# GRHV_4_Tube_v0_1.net
KiCad netlist of a schematic drawn in Altium Designer
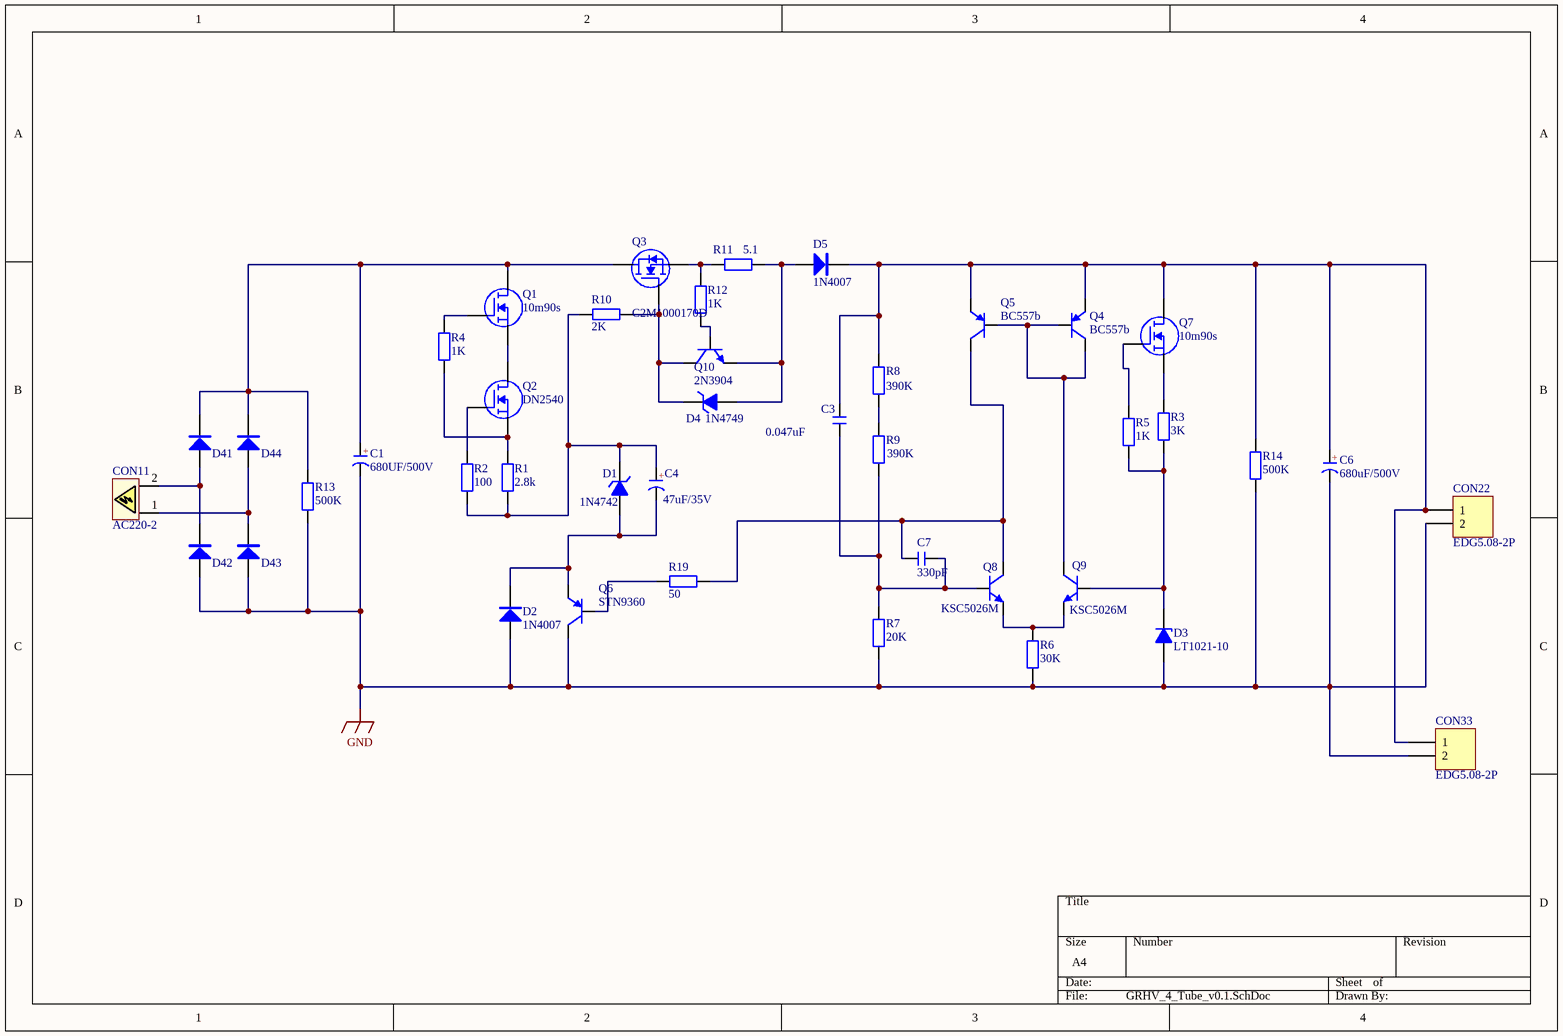
[diagram p0: GRHV_4_Tube_v0.1.SchDoc]

(export (version "E")
  (design (tool "Eeschema 10.0.6"))
  (components
    (comp (ref "C1")
      (value "680UF/500V")
      (footprint "CAP 11*35*60")
      (description "直插电解电容")
      (fields (field (name "版权归属") "源创客"))
      (libsource (lib "电阻-电容-电感") (part "C-CAP"))
    )
    (comp (ref "C3")
      (value "0.047uF")
      (footprint "CBB 15*18*11")
      (description "CBB电容")
      (fields (field (name "版权归属") "源创客"))
      (libsource (lib "电阻-电容-电感") (part "C-CBB"))
    )
    (comp (ref "C4")
      (value "47uF/35V")
      (footprint "CAP 5.0*10*12.5")
      (description "直插电解电容")
      (fields (field (name "版权归属") "源创客"))
      (libsource (lib "电阻-电容-电感") (part "C-CAP"))
    )
    (comp (ref "C6")
      (value "680uF/500V")
      (footprint "CAP 11*35*60")
      (description "直插电解电容")
      (fields (field (name "版权归属") "源创客"))
      (libsource (lib "电阻-电容-电感") (part "C-CAP"))
    )
    (comp (ref "C7")
      (value "330pF")
      (footprint "CBB 6.3*6.3*5")
      (description "CBB电容")
      (fields (field (name "版权归属") "源创客"))
      (libsource (lib "电阻-电容-电感") (part "C-CBB"))
    )
    (comp (ref "CON11")
      (value "AC220-2")
      (footprint "HX5.08-2S")
      (libsource (lib "Connectors") (part "AC220-2"))
    )
    (comp (ref "CON22")
      (value "EDG5.08-2P")
      (footprint "HX5.08-2L")
      (libsource (lib "Connectors") (part "EDG5.08-2P"))
    )
    (comp (ref "CON33")
      (value "EDG5.08-2P")
      (footprint "HX5.08-2L")
      (libsource (lib "Connectors") (part "EDG5.08-2P"))
    )
    (comp (ref "D1")
      (value "1N4742")
      (footprint "DO-41")
      (description "12V/1W稳压管")
      (libsource (lib "二极管-整流桥") (part "1N4742"))
    )
    (comp (ref "D2")
      (value "1N4007")
      (footprint "DO-41")
      (description "整流二极管")
      (fields (field (name "版权归属") "源创客"))
      (libsource (lib "二极管-整流桥") (part "1N4007"))
    )
    (comp (ref "D3")
      (value "LT1021-10")
      (footprint "DIP8-300_MH")
      (description "10V Precision Reference 2 Pin Config")
      (libsource (lib "电压参考") (part "LT1021-10-2P"))
    )
    (comp (ref "D4")
      (value "1N4749")
      (footprint "DO-41")
      (description "24V/1W稳压管")
      (libsource (lib "二极管-整流桥") (part "1N4749"))
    )
    (comp (ref "D5")
      (value "1N4007")
      (footprint "DO-41")
      (description "整流二极管")
      (fields (field (name "版权归属") "源创客"))
      (libsource (lib "二极管-整流桥") (part "1N4007"))
    )
    (comp (ref "D41")
      (value "VS-HFA08TB60-M3")
      (footprint "TO220AC")
      (description "Ultrafast Soft Recovery Diado 8A 600V")
      (libsource (lib "二极管-整流桥") (part "VS-HFA08TB60-M3"))
    )
    (comp (ref "D42")
      (value "VS-HFA08TB60-M3")
      (footprint "TO220AC")
      (description "Ultrafast Soft Recovery Diado 8A 600V")
      (libsource (lib "二极管-整流桥") (part "VS-HFA08TB60-M3"))
    )
    (comp (ref "D43")
      (value "VS-HFA08TB60-M3")
      (footprint "TO220AC")
      (description "Ultrafast Soft Recovery Diado 8A 600V")
      (libsource (lib "二极管-整流桥") (part "VS-HFA08TB60-M3"))
    )
    (comp (ref "D44")
      (value "VS-HFA08TB60-M3")
      (footprint "TO220AC")
      (description "Ultrafast Soft Recovery Diado 8A 600V")
      (libsource (lib "二极管-整流桥") (part "VS-HFA08TB60-M3"))
    )
    (comp (ref "Q1")
      (value "10m90s")
      (footprint "TO220H")
      (description "IC恒流源  900v 100ma")
      (libsource (lib "场效应管") (part "10m90s"))
    )
    (comp (ref "Q2")
      (value "DN2540")
      (footprint "TO220V")
      (description "N沟道耗尽型DMOS场效应管 400V/150ma")
      (libsource (lib "场效应管") (part "DN2540"))
    )
    (comp (ref "Q3")
      (value "C2M1000170D")
      (footprint "TO247H")
      (description "N沟道增强型 Z-FET MOS场效应管 1000v 5A")
      (libsource (lib "场效应管") (part "C2M1000170D"))
    )
    (comp (ref "Q4")
      (value "BC557b")
      (footprint "TO92A")
      (description "音频放大-PNP型")
      (libsource (lib "三极管") (part "BC557b"))
    )
    (comp (ref "Q5")
      (value "BC557b")
      (footprint "TO92A")
      (description "音频放大-PNP型")
      (libsource (lib "三极管") (part "BC557b"))
    )
    (comp (ref "Q6")
      (value "STN9360")
      (footprint "SOT223_L_Bottom")
      (description "High Voltage fast switching PNP型 600v 500ma")
      (libsource (lib "三极管") (part "STN9360"))
    )
    (comp (ref "Q7")
      (value "10m90s")
      (footprint "TO220H")
      (description "IC恒流源  900v 100ma")
      (libsource (lib "场效应管") (part "10m90s"))
    )
    (comp (ref "Q8")
      (value "KSC5026M")
      (footprint "TO126V")
      (description "High Speed Switch -NPN型")
      (libsource (lib "三极管") (part "KSC5026M"))
    )
    (comp (ref "Q9")
      (value "KSC5026M")
      (footprint "TO126V")
      (description "High Speed Switch -NPN型")
      (libsource (lib "三极管") (part "KSC5026M"))
    )
    (comp (ref "Q10")
      (value "2N3904")
      (footprint "TO92A")
      (description "通用三极管NPN型 40v 200ma")
      (libsource (lib "三极管") (part "2N3904"))
    )
    (comp (ref "R1")
      (value "2.8k")
      (footprint "RS 1W")
      (description "直插色环电阻")
      (fields (field (name "版权归属") "源创客"))
      (libsource (lib "电阻-电容-电感") (part "R-CRR"))
    )
    (comp (ref "R2")
      (value "100")
      (footprint "RS 1W")
      (description "直插色环电阻")
      (fields (field (name "版权归属") "源创客"))
      (libsource (lib "电阻-电容-电感") (part "R-CRR"))
    )
    (comp (ref "R3")
      (value "3K")
      (footprint "RS 1W")
      (description "直插色环电阻")
      (fields (field (name "版权归属") "源创客"))
      (libsource (lib "电阻-电容-电感") (part "R-CRR"))
    )
    (comp (ref "R4")
      (value "1K")
      (footprint "RS 1W")
      (description "直插色环电阻")
      (fields (field (name "版权归属") "源创客"))
      (libsource (lib "电阻-电容-电感") (part "R-CRR"))
    )
    (comp (ref "R5")
      (value "1K")
      (footprint "RS 1W")
      (description "直插色环电阻")
      (fields (field (name "版权归属") "源创客"))
      (libsource (lib "电阻-电容-电感") (part "R-CRR"))
    )
    (comp (ref "R6")
      (value "30K")
      (footprint "RS 1W")
      (description "直插色环电阻")
      (fields (field (name "版权归属") "源创客"))
      (libsource (lib "电阻-电容-电感") (part "R-CRR"))
    )
    (comp (ref "R7")
      (value "20K")
      (footprint "RS 1W")
      (description "直插色环电阻")
      (fields (field (name "版权归属") "源创客"))
      (libsource (lib "电阻-电容-电感") (part "R-CRR"))
    )
    (comp (ref "R8")
      (value "390K")
      (footprint "RS 1W")
      (description "直插色环电阻")
      (fields (field (name "版权归属") "源创客"))
      (libsource (lib "电阻-电容-电感") (part "R-CRR"))
    )
    (comp (ref "R9")
      (value "390K")
      (footprint "RS 1W")
      (description "直插色环电阻")
      (fields (field (name "版权归属") "源创客"))
      (libsource (lib "电阻-电容-电感") (part "R-CRR"))
    )
    (comp (ref "R10")
      (value "2K")
      (footprint "RS 1W")
      (description "直插色环电阻")
      (fields (field (name "版权归属") "源创客"))
      (libsource (lib "电阻-电容-电感") (part "R-CRR"))
    )
    (comp (ref "R11")
      (value "5.1")
      (footprint "RS 2W")
      (description "直插色环电阻")
      (fields (field (name "版权归属") "源创客"))
      (libsource (lib "电阻-电容-电感") (part "R-CRR"))
    )
    (comp (ref "R12")
      (value "1K")
      (footprint "RS 1W")
      (description "直插色环电阻")
      (fields (field (name "版权归属") "源创客"))
      (libsource (lib "电阻-电容-电感") (part "R-CRR"))
    )
    (comp (ref "R13")
      (value "500K")
      (footprint "RS 1W")
      (description "直插色环电阻")
      (fields (field (name "版权归属") "源创客"))
      (libsource (lib "电阻-电容-电感") (part "R-CRR"))
    )
    (comp (ref "R14")
      (value "500K")
      (footprint "RS 1W")
      (description "直插色环电阻")
      (fields (field (name "版权归属") "源创客"))
      (libsource (lib "电阻-电容-电感") (part "R-CRR"))
    )
    (comp (ref "R19")
      (value "50")
      (footprint "RS 1W")
      (description "直插色环电阻")
      (fields (field (name "版权归属") "源创客"))
      (libsource (lib "电阻-电容-电感") (part "R-CRR"))
    )
  )
  (nets
    (net (code "1") (name "GND") (class "Default")
      (node (ref "C1") (pin "2") (pinfunction "K_2") (pintype "passive"))
      (node (ref "C6") (pin "2") (pinfunction "K_2") (pintype "passive"))
      (node (ref "CON22") (pin "2") (pinfunction "2_2") (pintype "passive"))
      (node (ref "CON33") (pin "2") (pinfunction "2_2") (pintype "passive"))
      (node (ref "D2") (pin "1") (pinfunction "A_1") (pintype "passive"))
      (node (ref "D3") (pin "4") (pinfunction "A_4") (pintype "passive"))
      (node (ref "D42") (pin "2") (pinfunction "Anode_2") (pintype "passive"))
      (node (ref "D43") (pin "2") (pinfunction "Anode_2") (pintype "passive"))
      (node (ref "Q6") (pin "2") (pinfunction "C_2") (pintype "passive"))
      (node (ref "R13") (pin "1") (pinfunction "1_1") (pintype "passive"))
      (node (ref "R14") (pin "1") (pinfunction "1_1") (pintype "passive"))
      (node (ref "R6") (pin "1") (pinfunction "1_1") (pintype "passive"))
      (node (ref "R7") (pin "1") (pinfunction "1_1") (pintype "passive"))
    )
    (net (code "2") (name "Net-(C1-A)") (class "Default")
      (node (ref "C1") (pin "1") (pinfunction "A_1") (pintype "passive"))
      (node (ref "D41") (pin "1") (pinfunction "Cathode_1") (pintype "passive"))
      (node (ref "D44") (pin "1") (pinfunction "Cathode_1") (pintype "passive"))
      (node (ref "Q1") (pin "3") (pinfunction "D_3") (pintype "passive"))
      (node (ref "Q3") (pin "3") (pinfunction "D_3") (pintype "passive"))
      (node (ref "R13") (pin "2") (pinfunction "2_2") (pintype "passive"))
    )
    (net (code "3") (name "Net-(C4-A)") (class "Default")
      (node (ref "C4") (pin "1") (pinfunction "A_1") (pintype "passive"))
      (node (ref "D1") (pin "2") (pinfunction "K_2") (pintype "passive"))
      (node (ref "R1") (pin "1") (pinfunction "1_1") (pintype "passive"))
      (node (ref "R10") (pin "1") (pinfunction "1_1") (pintype "passive"))
      (node (ref "R2") (pin "1") (pinfunction "1_1") (pintype "passive"))
    )
    (net (code "4") (name "Net-(C4-K)") (class "Default")
      (node (ref "C4") (pin "2") (pinfunction "K_2") (pintype "passive"))
      (node (ref "D1") (pin "1") (pinfunction "A_1") (pintype "passive"))
      (node (ref "D2") (pin "2") (pinfunction "K_2") (pintype "passive"))
      (node (ref "Q6") (pin "1") (pinfunction "E_1") (pintype "passive"))
    )
    (net (code "5") (name "Net-(C6-A)") (class "Default")
      (node (ref "C3") (pin "2") (pinfunction "2_2") (pintype "passive"))
      (node (ref "C6") (pin "1") (pinfunction "A_1") (pintype "passive"))
      (node (ref "CON22") (pin "1") (pinfunction "1_1") (pintype "passive"))
      (node (ref "CON33") (pin "1") (pinfunction "1_1") (pintype "passive"))
      (node (ref "D5") (pin "2") (pinfunction "K_2") (pintype "passive"))
      (node (ref "Q4") (pin "1") (pinfunction "E_1") (pintype "passive"))
      (node (ref "Q5") (pin "1") (pinfunction "E_1") (pintype "passive"))
      (node (ref "Q7") (pin "3") (pinfunction "D_3") (pintype "passive"))
      (node (ref "R14") (pin "2") (pinfunction "2_2") (pintype "passive"))
      (node (ref "R8") (pin "2") (pinfunction "2_2") (pintype "passive"))
    )
    (net (code "6") (name "Net-(CON11-G)") (class "Default")
      (node (ref "CON11") (pin "2") (pinfunction "G_2") (pintype "passive"))
      (node (ref "D41") (pin "2") (pinfunction "Anode_2") (pintype "passive"))
      (node (ref "D42") (pin "1") (pinfunction "Cathode_1") (pintype "passive"))
    )
    (net (code "7") (name "Net-(CON11-L)") (class "Default")
      (node (ref "CON11") (pin "1") (pinfunction "L_1") (pintype "passive"))
      (node (ref "D43") (pin "1") (pinfunction "Cathode_1") (pintype "passive"))
      (node (ref "D44") (pin "2") (pinfunction "Anode_2") (pintype "passive"))
    )
    (net (code "8") (name "Net-(D3-K)") (class "Default")
      (node (ref "D3") (pin "6") (pinfunction "K_6") (pintype "passive"))
      (node (ref "Q9") (pin "3") (pinfunction "B_3") (pintype "passive"))
      (node (ref "R3") (pin "2") (pinfunction "2_2") (pintype "passive"))
      (node (ref "R5") (pin "2") (pinfunction "2_2") (pintype "passive"))
    )
    (net (code "9") (name "Net-(D4-A)") (class "Default")
      (node (ref "D4") (pin "1") (pinfunction "A_1") (pintype "passive"))
      (node (ref "D5") (pin "1") (pinfunction "A_1") (pintype "passive"))
      (node (ref "Q10") (pin "1") (pinfunction "E_1") (pintype "passive"))
      (node (ref "R11") (pin "2") (pinfunction "2_2") (pintype "passive"))
    )
    (net (code "10") (name "Net-(D4-K)") (class "Default")
      (node (ref "D4") (pin "2") (pinfunction "K_2") (pintype "passive"))
      (node (ref "Q10") (pin "2") (pinfunction "C_2") (pintype "passive"))
      (node (ref "Q3") (pin "2") (pinfunction "G_2") (pintype "passive"))
      (node (ref "R10") (pin "2") (pinfunction "2_2") (pintype "passive"))
    )
    (net (code "11") (name "Net-(Q1-G)") (class "Default")
      (node (ref "Q1") (pin "2") (pinfunction "G_2") (pintype "passive"))
      (node (ref "R4") (pin "2") (pinfunction "2_2") (pintype "passive"))
    )
    (net (code "12") (name "Net-(Q1-S)") (class "Default")
      (node (ref "Q1") (pin "1") (pinfunction "S_1") (pintype "passive"))
      (node (ref "Q2") (pin "3") (pinfunction "D_3") (pintype "passive"))
    )
    (net (code "13") (name "Net-(Q2-G)") (class "Default")
      (node (ref "Q2") (pin "2") (pinfunction "G_2") (pintype "passive"))
      (node (ref "R2") (pin "2") (pinfunction "2_2") (pintype "passive"))
    )
    (net (code "14") (name "Net-(Q2-S)") (class "Default")
      (node (ref "Q2") (pin "1") (pinfunction "S_1") (pintype "passive"))
      (node (ref "R1") (pin "2") (pinfunction "2_2") (pintype "passive"))
      (node (ref "R4") (pin "1") (pinfunction "1_1") (pintype "passive"))
    )
    (net (code "15") (name "Net-(Q3-S)") (class "Default")
      (node (ref "Q3") (pin "1") (pinfunction "S_1") (pintype "passive"))
      (node (ref "R11") (pin "1") (pinfunction "1_1") (pintype "passive"))
      (node (ref "R12") (pin "2") (pinfunction "2_2") (pintype "passive"))
    )
    (net (code "16") (name "Net-(Q4-B)") (class "Default")
      (node (ref "Q4") (pin "2") (pinfunction "C_2") (pintype "passive"))
      (node (ref "Q4") (pin "3") (pinfunction "B_3") (pintype "passive"))
      (node (ref "Q5") (pin "3") (pinfunction "B_3") (pintype "passive"))
      (node (ref "Q9") (pin "2") (pinfunction "C_2") (pintype "passive"))
    )
    (net (code "17") (name "Net-(Q5-C)") (class "Default")
      (node (ref "C7") (pin "2") (pinfunction "2_2") (pintype "passive"))
      (node (ref "Q5") (pin "2") (pinfunction "C_2") (pintype "passive"))
      (node (ref "Q8") (pin "2") (pinfunction "C_2") (pintype "passive"))
      (node (ref "R19") (pin "1") (pinfunction "1_1") (pintype "passive"))
    )
    (net (code "18") (name "Net-(Q6-B)") (class "Default")
      (node (ref "Q6") (pin "3") (pinfunction "B_3") (pintype "passive"))
      (node (ref "R19") (pin "2") (pinfunction "2_2") (pintype "passive"))
    )
    (net (code "19") (name "Net-(Q7-G)") (class "Default")
      (node (ref "Q7") (pin "2") (pinfunction "G_2") (pintype "passive"))
      (node (ref "R5") (pin "1") (pinfunction "1_1") (pintype "passive"))
    )
    (net (code "20") (name "Net-(Q7-S)") (class "Default")
      (node (ref "Q7") (pin "1") (pinfunction "S_1") (pintype "passive"))
      (node (ref "R3") (pin "1") (pinfunction "1_1") (pintype "passive"))
    )
    (net (code "21") (name "Net-(Q8-B)") (class "Default")
      (node (ref "C3") (pin "1") (pinfunction "1_1") (pintype "passive"))
      (node (ref "C7") (pin "1") (pinfunction "1_1") (pintype "passive"))
      (node (ref "Q8") (pin "3") (pinfunction "B_3") (pintype "passive"))
      (node (ref "R7") (pin "2") (pinfunction "2_2") (pintype "passive"))
      (node (ref "R9") (pin "1") (pinfunction "1_1") (pintype "passive"))
    )
    (net (code "22") (name "Net-(Q8-E)") (class "Default")
      (node (ref "Q8") (pin "1") (pinfunction "E_1") (pintype "passive"))
      (node (ref "Q9") (pin "1") (pinfunction "E_1") (pintype "passive"))
      (node (ref "R6") (pin "2") (pinfunction "2_2") (pintype "passive"))
    )
    (net (code "23") (name "Net-(Q10-B)") (class "Default")
      (node (ref "Q10") (pin "3") (pinfunction "B_3") (pintype "passive"))
      (node (ref "R12") (pin "1") (pinfunction "1_1") (pintype "passive"))
    )
    (net (code "24") (name "Net-(R8-Pad1)") (class "Default")
      (node (ref "R8") (pin "1") (pinfunction "1_1") (pintype "passive"))
      (node (ref "R9") (pin "2") (pinfunction "2_2") (pintype "passive"))
    )
  )
)
